# pgacontrol.net
KiCad netlist of a schematic drawn in EAGLE
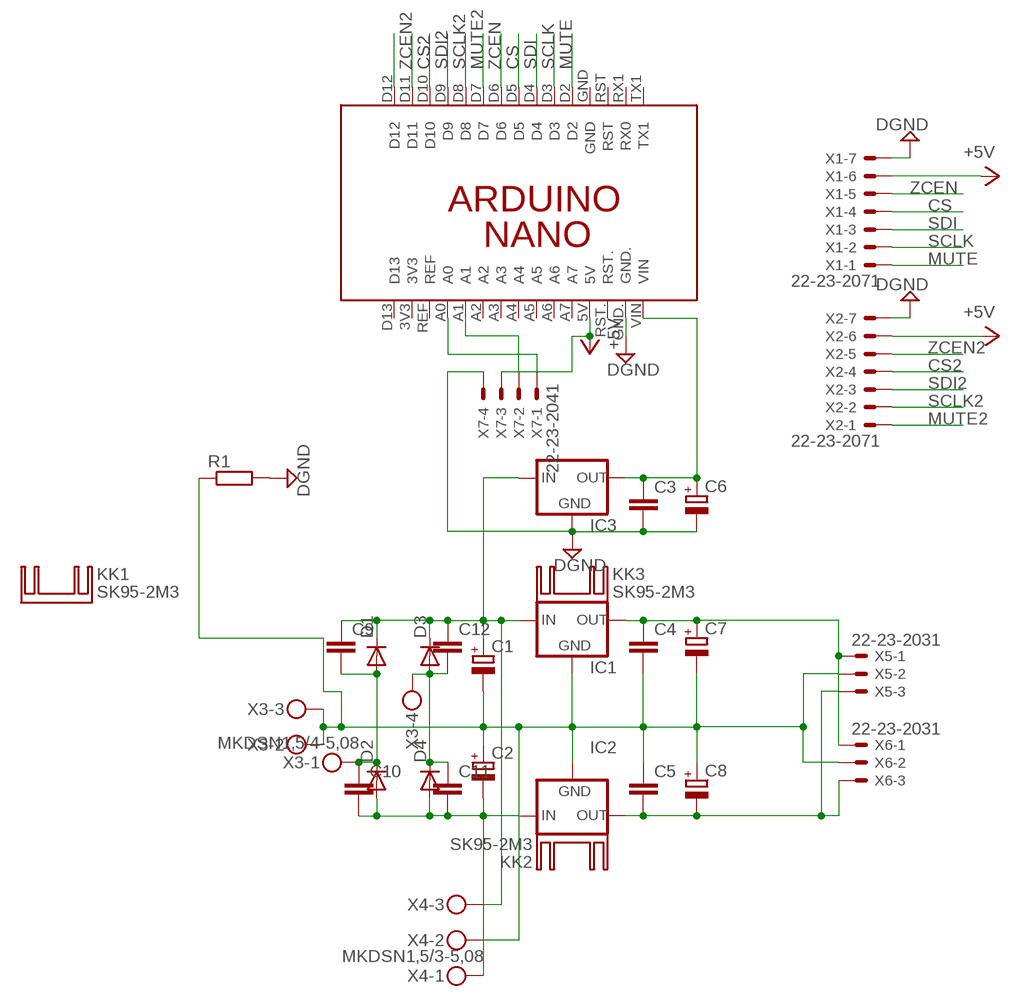
[diagram p0: schematic, sheet 1]

(export (version "E")
  (design (tool "Eeschema 10.0.6"))
  (components
    (comp (ref "C1")
      (value "CPOL-EUE7.5-18")
      (footprint "eagle-import:E7,5-18")
      (libsource (lib "eagle-import") (part "CPOL-EUE7.5-18"))
    )
    (comp (ref "C2")
      (value "CPOL-EUE7.5-18")
      (footprint "eagle-import:E7,5-18")
      (libsource (lib "eagle-import") (part "CPOL-EUE7.5-18"))
    )
    (comp (ref "C3")
      (value "C-EU050-030X075")
      (footprint "eagle-import:C050-030X075")
      (libsource (lib "eagle-import") (part "C-EU050-030X075"))
    )
    (comp (ref "C4")
      (value "C-EU050-030X075")
      (footprint "eagle-import:C050-030X075")
      (libsource (lib "eagle-import") (part "C-EU050-030X075"))
    )
    (comp (ref "C5")
      (value "C-EU050-030X075")
      (footprint "eagle-import:C050-030X075")
      (libsource (lib "eagle-import") (part "C-EU050-030X075"))
    )
    (comp (ref "C6")
      (value "CPOL-EUE3.5-8")
      (footprint "eagle-import:E3,5-8")
      (libsource (lib "eagle-import") (part "CPOL-EUE3.5-8"))
    )
    (comp (ref "C7")
      (value "CPOL-EUE3.5-8")
      (footprint "eagle-import:E3,5-8")
      (libsource (lib "eagle-import") (part "CPOL-EUE3.5-8"))
    )
    (comp (ref "C8")
      (value "CPOL-EUE3.5-8")
      (footprint "eagle-import:E3,5-8")
      (libsource (lib "eagle-import") (part "CPOL-EUE3.5-8"))
    )
    (comp (ref "C9")
      (value "C-EU050-030X075")
      (footprint "eagle-import:C050-030X075")
      (libsource (lib "eagle-import") (part "C-EU050-030X075"))
    )
    (comp (ref "C10")
      (value "C-EU050-030X075")
      (footprint "eagle-import:C050-030X075")
      (libsource (lib "eagle-import") (part "C-EU050-030X075"))
    )
    (comp (ref "C11")
      (value "C-EU050-030X075")
      (footprint "eagle-import:C050-030X075")
      (libsource (lib "eagle-import") (part "C-EU050-030X075"))
    )
    (comp (ref "C12")
      (value "C-EU050-030X075")
      (footprint "eagle-import:C050-030X075")
      (libsource (lib "eagle-import") (part "C-EU050-030X075"))
    )
    (comp (ref "D1")
      (value "1N4148DO35-10")
      (footprint "eagle-import:DO35-10")
      (libsource (lib "eagle-import") (part "1N4148DO35-10"))
    )
    (comp (ref "D2")
      (value "1N4148DO35-10")
      (footprint "eagle-import:DO35-10")
      (libsource (lib "eagle-import") (part "1N4148DO35-10"))
    )
    (comp (ref "D3")
      (value "1N4148DO35-10")
      (footprint "eagle-import:DO35-10")
      (libsource (lib "eagle-import") (part "1N4148DO35-10"))
    )
    (comp (ref "D4")
      (value "1N4148DO35-10")
      (footprint "eagle-import:DO35-10")
      (libsource (lib "eagle-import") (part "1N4148DO35-10"))
    )
    (comp (ref "IC1")
      (value "78XXS")
      (footprint "eagle-import:78XXS")
      (libsource (lib "eagle-import") (part "78XXS"))
    )
    (comp (ref "IC2")
      (value "79XXS")
      (footprint "eagle-import:79XXS")
      (libsource (lib "eagle-import") (part "79XXS"))
    )
    (comp (ref "IC3")
      (value "78XXS")
      (footprint "eagle-import:78XXS")
      (libsource (lib "eagle-import") (part "78XXS"))
    )
    (comp (ref "KK1")
      (value "SK95-2M3")
      (footprint "eagle-import:SK95-2M3")
      (libsource (lib "eagle-import") (part "SK95-2M3"))
    )
    (comp (ref "KK2")
      (value "SK95-2M3")
      (footprint "eagle-import:SK95-2M3")
      (libsource (lib "eagle-import") (part "SK95-2M3"))
    )
    (comp (ref "KK3")
      (value "SK95-2M3")
      (footprint "eagle-import:SK95-2M3")
      (libsource (lib "eagle-import") (part "SK95-2M3"))
    )
    (comp (ref "PCB1")
      (value "ARDUINO_NANO")
      (footprint "eagle-import:ARDUINO_NANO")
      (libsource (lib "eagle-import") (part "ARDUINO_NANO"))
    )
    (comp (ref "R1")
      (value "R-EU_0207/7")
      (footprint "eagle-import:0207_7")
      (libsource (lib "eagle-import") (part "R-EU_0207/7"))
    )
    (comp (ref "X1")
      (value "22-23-2071")
      (footprint "eagle-import:22-23-2071")
      (fields (field (name "MF") "MOLEX"))
      (libsource (lib "eagle-import") (part "22-23-2071"))
    )
    (comp (ref "X2")
      (value "22-23-2071")
      (footprint "eagle-import:22-23-2071")
      (fields (field (name "MF") "MOLEX"))
      (libsource (lib "eagle-import") (part "22-23-2071"))
    )
    (comp (ref "X3")
      (value "MKDSN1,5/4-5,08")
      (footprint "eagle-import:MKDSN1,5_4-5,08")
      (libsource (lib "eagle-import") (part "MKDSN1,5/4-5,08"))
    )
    (comp (ref "X4")
      (value "MKDSN1,5/3-5,08")
      (footprint "eagle-import:MKDSN1,5_3-5,08")
      (libsource (lib "eagle-import") (part "MKDSN1,5/3-5,08"))
    )
    (comp (ref "X5")
      (value "22-23-2031")
      (footprint "eagle-import:22-23-2031")
      (fields (field (name "MF") "MOLEX"))
      (libsource (lib "eagle-import") (part "22-23-2031"))
    )
    (comp (ref "X6")
      (value "22-23-2031")
      (footprint "eagle-import:22-23-2031")
      (fields (field (name "MF") "MOLEX"))
      (libsource (lib "eagle-import") (part "22-23-2031"))
    )
    (comp (ref "X7")
      (value "22-23-2041")
      (footprint "eagle-import:22-23-2041")
      (fields (field (name "MF") "MOLEX"))
      (libsource (lib "eagle-import") (part "22-23-2041"))
    )
  )
  (nets
    (net (code "1") (name "+5V") (class "Default")
      (node (ref "PCB1") (pin "5V") (pinfunction "5V_5V") (pintype "bidirectional"))
      (node (ref "X1") (pin "6") (pinfunction "S_6") (pintype "passive"))
      (node (ref "X2") (pin "6") (pinfunction "S_6") (pintype "passive"))
      (node (ref "X7") (pin "3") (pinfunction "S_3") (pintype "passive"))
    )
    (net (code "2") (name "/CS") (class "Default")
      (node (ref "PCB1") (pin "D5") (pinfunction "D5_D5") (pintype "bidirectional"))
      (node (ref "X1") (pin "4") (pinfunction "S_4") (pintype "passive"))
    )
    (net (code "3") (name "/CS2") (class "Default")
      (node (ref "PCB1") (pin "D10") (pinfunction "D10_D10") (pintype "bidirectional"))
      (node (ref "X2") (pin "4") (pinfunction "S_4") (pintype "passive"))
    )
    (net (code "4") (name "/MUTE") (class "Default")
      (node (ref "PCB1") (pin "D2") (pinfunction "D2_D2") (pintype "bidirectional"))
      (node (ref "X1") (pin "1") (pinfunction "S_1") (pintype "passive"))
    )
    (net (code "5") (name "/MUTE2") (class "Default")
      (node (ref "PCB1") (pin "D7") (pinfunction "D7_D7") (pintype "bidirectional"))
      (node (ref "X2") (pin "1") (pinfunction "S_1") (pintype "passive"))
    )
    (net (code "6") (name "/SCLK") (class "Default")
      (node (ref "PCB1") (pin "D3") (pinfunction "D3_D3") (pintype "bidirectional"))
      (node (ref "X1") (pin "2") (pinfunction "S_2") (pintype "passive"))
    )
    (net (code "7") (name "/SCLK2") (class "Default")
      (node (ref "PCB1") (pin "D8") (pinfunction "D8_D8") (pintype "bidirectional"))
      (node (ref "X2") (pin "2") (pinfunction "S_2") (pintype "passive"))
    )
    (net (code "8") (name "/SDI") (class "Default")
      (node (ref "PCB1") (pin "D4") (pinfunction "D4_D4") (pintype "bidirectional"))
      (node (ref "X1") (pin "3") (pinfunction "S_3") (pintype "passive"))
    )
    (net (code "9") (name "/SDI2") (class "Default")
      (node (ref "PCB1") (pin "D9") (pinfunction "D9_D9") (pintype "bidirectional"))
      (node (ref "X2") (pin "3") (pinfunction "S_3") (pintype "passive"))
    )
    (net (code "10") (name "/ZCEN") (class "Default")
      (node (ref "PCB1") (pin "D6") (pinfunction "D6_D6") (pintype "bidirectional"))
      (node (ref "X1") (pin "5") (pinfunction "S_5") (pintype "passive"))
    )
    (net (code "11") (name "/ZCEN2") (class "Default")
      (node (ref "PCB1") (pin "D11") (pinfunction "D11_D11") (pintype "bidirectional"))
      (node (ref "X2") (pin "5") (pinfunction "S_5") (pintype "passive"))
    )
    (net (code "12") (name "DGND") (class "Default")
      (node (ref "C3") (pin "2") (pinfunction "2_2") (pintype "passive"))
      (node (ref "C6") (pin "-") (pinfunction "-_-") (pintype "passive"))
      (node (ref "IC3") (pin "GND") (pinfunction "GND_GND") (pintype "input"))
      (node (ref "PCB1") (pin "GND.") (pinfunction "GND._GND.") (pintype "bidirectional"))
      (node (ref "R1") (pin "2") (pinfunction "2_2") (pintype "passive"))
      (node (ref "X1") (pin "7") (pinfunction "S_7") (pintype "passive"))
      (node (ref "X2") (pin "7") (pinfunction "S_7") (pintype "passive"))
      (node (ref "X7") (pin "4") (pinfunction "S_4") (pintype "passive"))
    )
    (net (code "13") (name "Net-(C3-Pad1)") (class "Default")
      (node (ref "C3") (pin "1") (pinfunction "1_1") (pintype "passive"))
      (node (ref "C6") (pin "+") (pinfunction "+_+") (pintype "passive"))
      (node (ref "IC3") (pin "OUT") (pinfunction "OUT_OUT") (pintype "passive"))
      (node (ref "PCB1") (pin "VIN") (pinfunction "VIN_VIN") (pintype "bidirectional"))
    )
    (net (code "14") (name "Net-(X3A-KL)") (class "Default")
      (node (ref "C10") (pin "1") (pinfunction "1_1") (pintype "passive"))
      (node (ref "C9") (pin "2") (pinfunction "2_2") (pintype "passive"))
      (node (ref "D1") (pin "A") (pinfunction "A_A") (pintype "passive"))
      (node (ref "D2") (pin "C") (pinfunction "C_C") (pintype "passive"))
      (node (ref "X3") (pin "1") (pinfunction "KL_1") (pintype "passive"))
    )
    (net (code "15") (name "Net-(X3B-KL)") (class "Default")
      (node (ref "C1") (pin "-") (pinfunction "-_-") (pintype "passive"))
      (node (ref "C2") (pin "+") (pinfunction "+_+") (pintype "passive"))
      (node (ref "C4") (pin "2") (pinfunction "2_2") (pintype "passive"))
      (node (ref "C5") (pin "1") (pinfunction "1_1") (pintype "passive"))
      (node (ref "C7") (pin "-") (pinfunction "-_-") (pintype "passive"))
      (node (ref "C8") (pin "+") (pinfunction "+_+") (pintype "passive"))
      (node (ref "IC1") (pin "GND") (pinfunction "GND_GND") (pintype "input"))
      (node (ref "IC2") (pin "GND") (pinfunction "GND_GND") (pintype "input"))
      (node (ref "R1") (pin "1") (pinfunction "1_1") (pintype "passive"))
      (node (ref "X3") (pin "2") (pinfunction "KL_2") (pintype "passive"))
      (node (ref "X3") (pin "3") (pinfunction "KL_3") (pintype "passive"))
      (node (ref "X4") (pin "2") (pinfunction "KL_2") (pintype "passive"))
      (node (ref "X5") (pin "2") (pinfunction "S_2") (pintype "passive"))
      (node (ref "X6") (pin "2") (pinfunction "S_2") (pintype "passive"))
    )
    (net (code "16") (name "Net-(X3D-KL)") (class "Default")
      (node (ref "C11") (pin "1") (pinfunction "1_1") (pintype "passive"))
      (node (ref "C12") (pin "2") (pinfunction "2_2") (pintype "passive"))
      (node (ref "D3") (pin "A") (pinfunction "A_A") (pintype "passive"))
      (node (ref "D4") (pin "C") (pinfunction "C_C") (pintype "passive"))
      (node (ref "X3") (pin "4") (pinfunction "KL_4") (pintype "passive"))
    )
    (net (code "17") (name "Net-(X4A-KL)") (class "Default")
      (node (ref "C10") (pin "2") (pinfunction "2_2") (pintype "passive"))
      (node (ref "C11") (pin "2") (pinfunction "2_2") (pintype "passive"))
      (node (ref "C2") (pin "-") (pinfunction "-_-") (pintype "passive"))
      (node (ref "D2") (pin "A") (pinfunction "A_A") (pintype "passive"))
      (node (ref "D4") (pin "A") (pinfunction "A_A") (pintype "passive"))
      (node (ref "IC2") (pin "IN") (pinfunction "IN_IN") (pintype "input"))
      (node (ref "X4") (pin "1") (pinfunction "KL_1") (pintype "passive"))
    )
    (net (code "18") (name "Net-(X4C-KL)") (class "Default")
      (node (ref "C1") (pin "+") (pinfunction "+_+") (pintype "passive"))
      (node (ref "C12") (pin "1") (pinfunction "1_1") (pintype "passive"))
      (node (ref "C9") (pin "1") (pinfunction "1_1") (pintype "passive"))
      (node (ref "D1") (pin "C") (pinfunction "C_C") (pintype "passive"))
      (node (ref "D3") (pin "C") (pinfunction "C_C") (pintype "passive"))
      (node (ref "IC1") (pin "IN") (pinfunction "IN_IN") (pintype "input"))
      (node (ref "IC3") (pin "IN") (pinfunction "IN_IN") (pintype "input"))
      (node (ref "X4") (pin "3") (pinfunction "KL_3") (pintype "passive"))
    )
    (net (code "19") (name "Net-(X5A-S)") (class "Default")
      (node (ref "C4") (pin "1") (pinfunction "1_1") (pintype "passive"))
      (node (ref "C7") (pin "+") (pinfunction "+_+") (pintype "passive"))
      (node (ref "IC1") (pin "OUT") (pinfunction "OUT_OUT") (pintype "passive"))
      (node (ref "X5") (pin "1") (pinfunction "S_1") (pintype "passive"))
      (node (ref "X6") (pin "1") (pinfunction "S_1") (pintype "passive"))
    )
    (net (code "20") (name "Net-(X5C-S)") (class "Default")
      (node (ref "C5") (pin "2") (pinfunction "2_2") (pintype "passive"))
      (node (ref "C8") (pin "-") (pinfunction "-_-") (pintype "passive"))
      (node (ref "IC2") (pin "OUT") (pinfunction "OUT_OUT") (pintype "passive"))
      (node (ref "X5") (pin "3") (pinfunction "S_3") (pintype "passive"))
      (node (ref "X6") (pin "3") (pinfunction "S_3") (pintype "passive"))
    )
    (net (code "21") (name "Net-(X7A-S)") (class "Default")
      (node (ref "PCB1") (pin "A0") (pinfunction "A0_A0") (pintype "bidirectional"))
      (node (ref "X7") (pin "1") (pinfunction "S_1") (pintype "passive"))
    )
    (net (code "22") (name "Net-(X7B-S)") (class "Default")
      (node (ref "PCB1") (pin "A1") (pinfunction "A1_A1") (pintype "bidirectional"))
      (node (ref "X7") (pin "2") (pinfunction "S_2") (pintype "passive"))
    )
    (net (code "23") (name "unconnected-(PCB1-Pad3V3)") (class "Default")
      (node (ref "PCB1") (pin "3V3") (pinfunction "3V3_3V3") (pintype "bidirectional"))
    )
    (net (code "24") (name "unconnected-(PCB1-PadA2)") (class "Default")
      (node (ref "PCB1") (pin "A2") (pinfunction "A2_A2") (pintype "bidirectional"))
    )
    (net (code "25") (name "unconnected-(PCB1-PadA3)") (class "Default")
      (node (ref "PCB1") (pin "A3") (pinfunction "A3_A3") (pintype "bidirectional"))
    )
    (net (code "26") (name "unconnected-(PCB1-PadA4)") (class "Default")
      (node (ref "PCB1") (pin "A4") (pinfunction "A4_A4") (pintype "bidirectional"))
    )
    (net (code "27") (name "unconnected-(PCB1-PadA5)") (class "Default")
      (node (ref "PCB1") (pin "A5") (pinfunction "A5_A5") (pintype "bidirectional"))
    )
    (net (code "28") (name "unconnected-(PCB1-PadA6)") (class "Default")
      (node (ref "PCB1") (pin "A6") (pinfunction "A6_A6") (pintype "bidirectional"))
    )
    (net (code "29") (name "unconnected-(PCB1-PadA7)") (class "Default")
      (node (ref "PCB1") (pin "A7") (pinfunction "A7_A7") (pintype "bidirectional"))
    )
    (net (code "30") (name "unconnected-(PCB1-PadD12)") (class "Default")
      (node (ref "PCB1") (pin "D12") (pinfunction "D12_D12") (pintype "bidirectional"))
    )
    (net (code "31") (name "unconnected-(PCB1-PadD13)") (class "Default")
      (node (ref "PCB1") (pin "D13") (pinfunction "D13_D13") (pintype "bidirectional"))
    )
    (net (code "32") (name "unconnected-(PCB1-PadGND)") (class "Default")
      (node (ref "PCB1") (pin "GND") (pinfunction "GND_GND") (pintype "bidirectional"))
    )
    (net (code "33") (name "unconnected-(PCB1-PadREF)") (class "Default")
      (node (ref "PCB1") (pin "REF") (pinfunction "REF_REF") (pintype "bidirectional"))
    )
    (net (code "34") (name "unconnected-(PCB1-PadRST)") (class "Default")
      (node (ref "PCB1") (pin "RST") (pinfunction "RST_RST") (pintype "bidirectional"))
    )
    (net (code "35") (name "unconnected-(PCB1-PadRST.)") (class "Default")
      (node (ref "PCB1") (pin "RST.") (pinfunction "RST._RST.") (pintype "bidirectional"))
    )
    (net (code "36") (name "unconnected-(PCB1-PadTX1)") (class "Default")
      (node (ref "PCB1") (pin "TX1") (pinfunction "TX1_TX1") (pintype "bidirectional"))
    )
    (net (code "37") (name "unconnected-(PCB1-RX0-PadRX1)") (class "Default")
      (node (ref "PCB1") (pin "RX1") (pinfunction "RX0_RX1") (pintype "bidirectional"))
    )
  )
)
